# WizFi_Baseboard.net
KiCad netlist of a schematic drawn in EAGLE
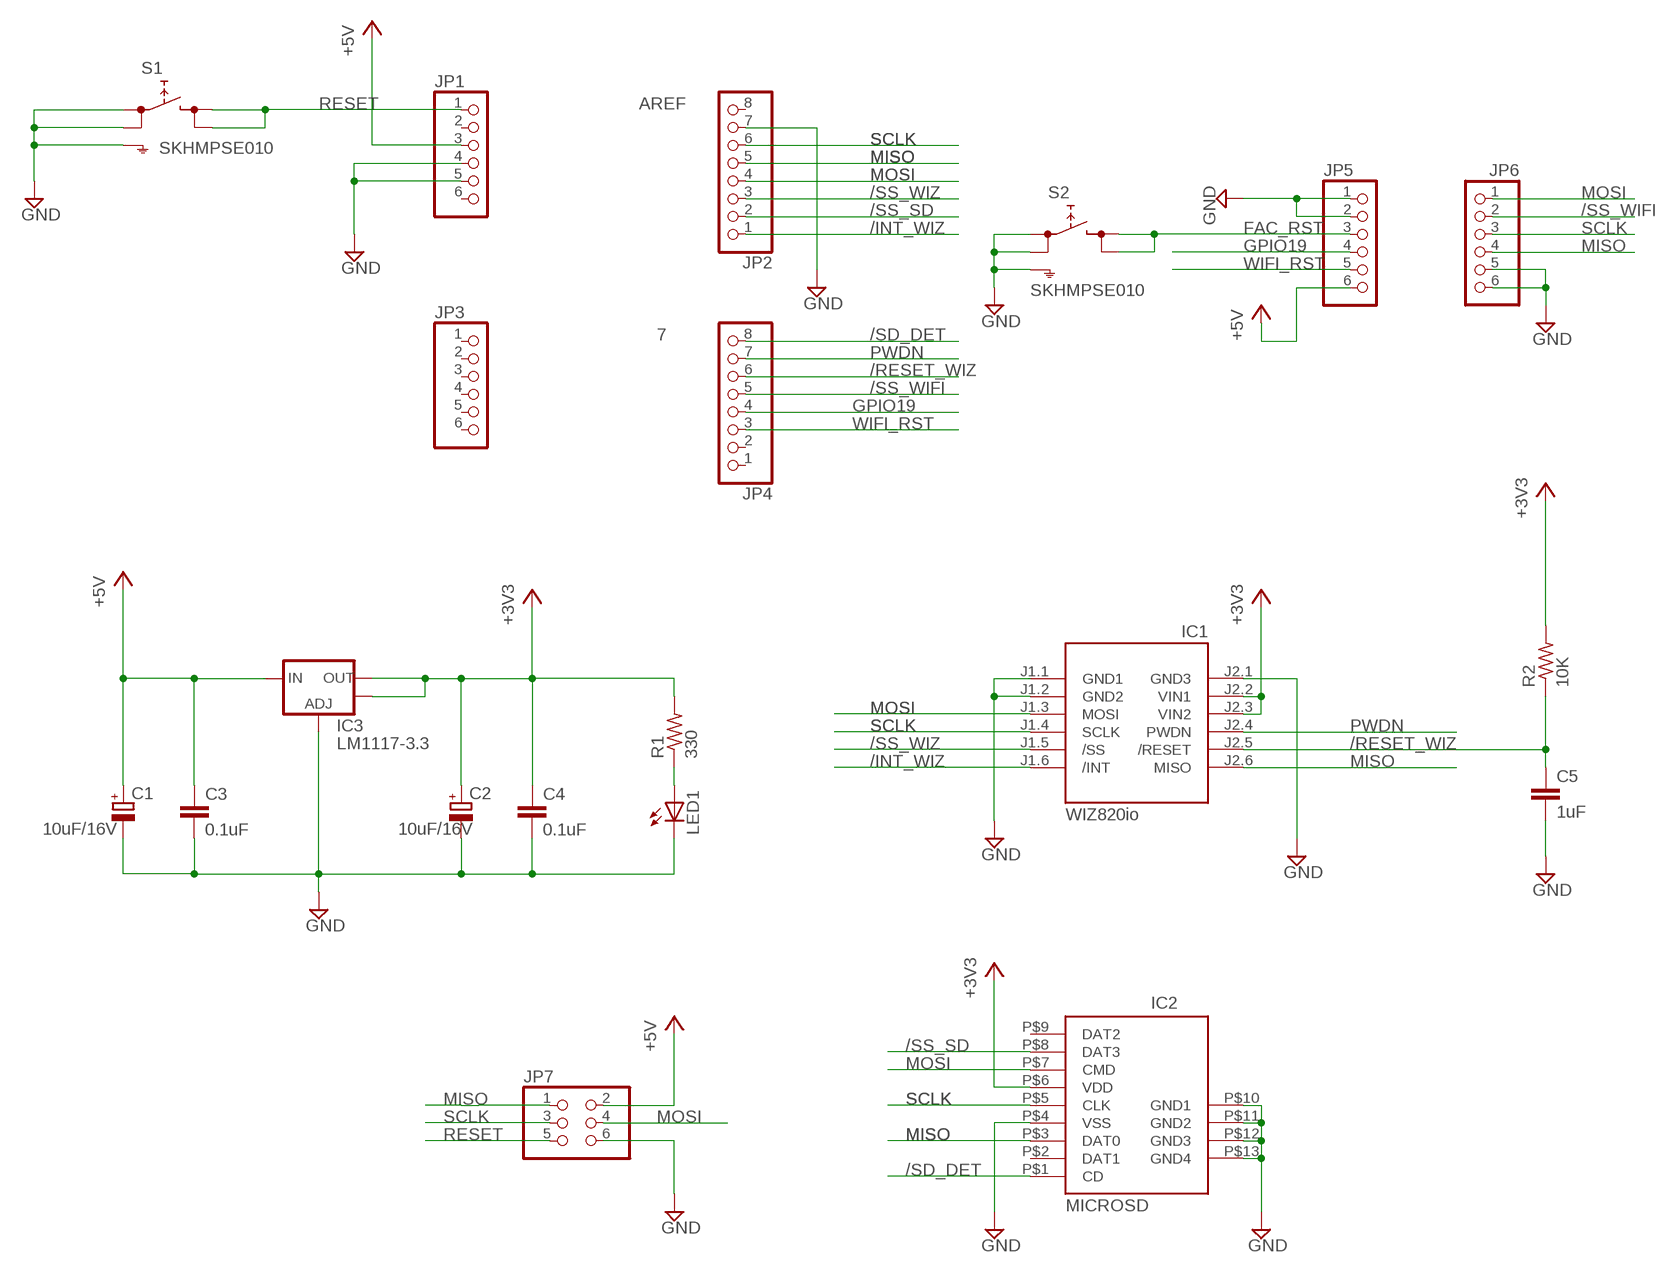
[diagram p0: schematic, sheet 1]

(export (version "E")
  (design (tool "Eeschema 10.0.6"))
  (components
    (comp (ref "C1")
      (value "10uF/16V")
      (footprint "eagle-import:CT3216")
      (libsource (lib "eagle-import") (part "CPOL-EUCT3216"))
    )
    (comp (ref "C2")
      (value "10uF/16V")
      (footprint "eagle-import:CT3216")
      (libsource (lib "eagle-import") (part "CPOL-EUCT3216"))
    )
    (comp (ref "C3")
      (value "0.1uF")
      (footprint "eagle-import:C0805")
      (libsource (lib "eagle-import") (part "C-EUC0805"))
    )
    (comp (ref "C4")
      (value "0.1uF")
      (footprint "eagle-import:C0805")
      (libsource (lib "eagle-import") (part "C-EUC0805"))
    )
    (comp (ref "C5")
      (value "1uF")
      (footprint "eagle-import:C0805")
      (libsource (lib "eagle-import") (part "C-EUC0805"))
    )
    (comp (ref "IC1")
      (value "WIZ820io")
      (footprint "eagle-import:WIZ820IO")
      (libsource (lib "eagle-import") (part "WIZ820IO_DEVICE'DUAL-IN-LINE-STAMP'"))
    )
    (comp (ref "IC2")
      (value "MICROSD")
      (footprint "eagle-import:MSDPAC")
      (libsource (lib "eagle-import") (part "MICROSD"))
    )
    (comp (ref "IC3")
      (value "LM1117-3.3")
      (footprint "eagle-import:SOT223")
      (libsource (lib "eagle-import") (part "V_REG_LM1117SOT223"))
    )
    (comp (ref "JP1")
      (value "PINHD-1X6")
      (footprint "eagle-import:1X06")
      (libsource (lib "eagle-import") (part "PINHD-1X6"))
    )
    (comp (ref "JP2")
      (value "PINHD-1X8")
      (footprint "eagle-import:1X08")
      (libsource (lib "eagle-import") (part "PINHD-1X8"))
    )
    (comp (ref "JP3")
      (value "PINHD-1X6")
      (footprint "eagle-import:1X06")
      (libsource (lib "eagle-import") (part "PINHD-1X6"))
    )
    (comp (ref "JP4")
      (value "PINHD-1X8")
      (footprint "eagle-import:1X08")
      (libsource (lib "eagle-import") (part "PINHD-1X8"))
    )
    (comp (ref "JP5")
      (value "PINHD-1X6")
      (footprint "eagle-import:1X06")
      (libsource (lib "eagle-import") (part "PINHD-1X6"))
    )
    (comp (ref "JP6")
      (value "PINHD-1X6")
      (footprint "eagle-import:1X06")
      (libsource (lib "eagle-import") (part "PINHD-1X6"))
    )
    (comp (ref "JP7")
      (value "PINHD-2X3")
      (footprint "eagle-import:2X03")
      (libsource (lib "eagle-import") (part "PINHD-2X3"))
    )
    (comp (ref "LED1")
      (value "LEDCHIP-LED0805")
      (footprint "eagle-import:CHIP-LED0805")
      (libsource (lib "eagle-import") (part "LEDCHIP-LED0805"))
    )
    (comp (ref "R1")
      (value "330")
      (footprint "eagle-import:R0805")
      (libsource (lib "eagle-import") (part "R-US_R0805"))
    )
    (comp (ref "R2")
      (value "10K")
      (footprint "eagle-import:R0805")
      (libsource (lib "eagle-import") (part "R-US_R0805"))
    )
    (comp (ref "S1")
      (value "SKHMPSE010")
      (footprint "eagle-import:SKHMPXE010")
      (libsource (lib "eagle-import") (part "SKHMPE010S"))
    )
    (comp (ref "S2")
      (value "SKHMPSE010")
      (footprint "eagle-import:SKHMPXE010")
      (libsource (lib "eagle-import") (part "SKHMPE010S"))
    )
  )
  (nets
    (net (code "1") (name "+3V3") (class "Default")
      (node (ref "C2") (pin "+") (pinfunction "+_+") (pintype "passive"))
      (node (ref "C4") (pin "1") (pinfunction "1_1") (pintype "passive"))
      (node (ref "IC1") (pin "J2.2") (pinfunction "VIN1_J2.2") (pintype "power_in"))
      (node (ref "IC1") (pin "J2.3") (pinfunction "VIN2_J2.3") (pintype "power_in"))
      (node (ref "IC2") (pin "P$6") (pinfunction "VDD_P$6") (pintype "power_in"))
      (node (ref "IC3") (pin "2") (pinfunction "OUT_2") (pintype "output"))
      (node (ref "IC3") (pin "4") (pinfunction "OUT_4") (pintype "output"))
      (node (ref "R1") (pin "2") (pinfunction "2_2") (pintype "passive"))
      (node (ref "R2") (pin "2") (pinfunction "2_2") (pintype "passive"))
    )
    (net (code "2") (name "+5V") (class "Default")
      (node (ref "C1") (pin "+") (pinfunction "+_+") (pintype "passive"))
      (node (ref "C3") (pin "1") (pinfunction "1_1") (pintype "passive"))
      (node (ref "IC3") (pin "3") (pinfunction "IN_3") (pintype "input"))
      (node (ref "JP1") (pin "3") (pinfunction "3_3") (pintype "passive"))
      (node (ref "JP5") (pin "6") (pinfunction "6_6") (pintype "passive"))
      (node (ref "JP7") (pin "2") (pinfunction "2_2") (pintype "passive"))
    )
    (net (code "3") (name "/FAC_RST") (class "Default")
      (node (ref "JP5") (pin "3") (pinfunction "3_3") (pintype "passive"))
      (node (ref "S2") (pin "3") (pinfunction "2.1_3") (pintype "passive"))
      (node (ref "S2") (pin "4") (pinfunction "2.2_4") (pintype "passive"))
    )
    (net (code "4") (name "/GPIO19") (class "Default")
      (node (ref "JP4") (pin "4") (pinfunction "4_4") (pintype "passive"))
      (node (ref "JP5") (pin "4") (pinfunction "4_4") (pintype "passive"))
    )
    (net (code "5") (name "/MISO") (class "Default")
      (node (ref "IC1") (pin "J2.6") (pinfunction "MISO_J2.6") (pintype "output"))
      (node (ref "IC2") (pin "P$3") (pinfunction "DAT0_P$3") (pintype "bidirectional"))
      (node (ref "JP2") (pin "5") (pinfunction "5_5") (pintype "passive"))
      (node (ref "JP6") (pin "4") (pinfunction "4_4") (pintype "passive"))
      (node (ref "JP7") (pin "1") (pinfunction "1_1") (pintype "passive"))
    )
    (net (code "6") (name "/MOSI") (class "Default")
      (node (ref "IC1") (pin "J1.3") (pinfunction "MOSI_J1.3") (pintype "input"))
      (node (ref "IC2") (pin "P$7") (pinfunction "CMD_P$7") (pintype "input"))
      (node (ref "JP2") (pin "4") (pinfunction "4_4") (pintype "passive"))
      (node (ref "JP6") (pin "1") (pinfunction "1_1") (pintype "passive"))
      (node (ref "JP7") (pin "4") (pinfunction "4_4") (pintype "passive"))
    )
    (net (code "7") (name "/PWDN") (class "Default")
      (node (ref "IC1") (pin "J2.4") (pinfunction "PWDN_J2.4") (pintype "input"))
      (node (ref "JP4") (pin "7") (pinfunction "7_7") (pintype "passive"))
    )
    (net (code "8") (name "/RESET") (class "Default")
      (node (ref "JP1") (pin "1") (pinfunction "1_1") (pintype "passive"))
      (node (ref "JP7") (pin "5") (pinfunction "5_5") (pintype "passive"))
      (node (ref "S1") (pin "3") (pinfunction "2.1_3") (pintype "passive"))
      (node (ref "S1") (pin "4") (pinfunction "2.2_4") (pintype "passive"))
    )
    (net (code "9") (name "/SCLK") (class "Default")
      (node (ref "IC1") (pin "J1.4") (pinfunction "SCLK_J1.4") (pintype "input"))
      (node (ref "IC2") (pin "P$5") (pinfunction "CLK_P$5") (pintype "input"))
      (node (ref "JP2") (pin "6") (pinfunction "6_6") (pintype "passive"))
      (node (ref "JP6") (pin "3") (pinfunction "3_3") (pintype "passive"))
      (node (ref "JP7") (pin "3") (pinfunction "3_3") (pintype "passive"))
    )
    (net (code "10") (name "/WIFI_RST") (class "Default")
      (node (ref "JP4") (pin "3") (pinfunction "3_3") (pintype "passive"))
      (node (ref "JP5") (pin "5") (pinfunction "5_5") (pintype "passive"))
    )
    (net (code "11") (name "/{slash}INT_WIZ") (class "Default")
      (node (ref "IC1") (pin "J1.6") (pinfunction "/INT_J1.6") (pintype "output"))
      (node (ref "JP2") (pin "1") (pinfunction "1_1") (pintype "passive"))
    )
    (net (code "12") (name "/{slash}RESET_WIZ") (class "Default")
      (node (ref "C5") (pin "1") (pinfunction "1_1") (pintype "passive"))
      (node (ref "IC1") (pin "J2.5") (pinfunction "/RESET_J2.5") (pintype "input"))
      (node (ref "JP4") (pin "6") (pinfunction "6_6") (pintype "passive"))
      (node (ref "R2") (pin "1") (pinfunction "1_1") (pintype "passive"))
    )
    (net (code "13") (name "/{slash}SD_DET") (class "Default")
      (node (ref "IC2") (pin "P$1") (pinfunction "CD_P$1") (pintype "bidirectional"))
      (node (ref "JP4") (pin "8") (pinfunction "8_8") (pintype "passive"))
    )
    (net (code "14") (name "/{slash}SS_SD") (class "Default")
      (node (ref "IC2") (pin "P$8") (pinfunction "DAT3_P$8") (pintype "bidirectional"))
      (node (ref "JP2") (pin "2") (pinfunction "2_2") (pintype "passive"))
    )
    (net (code "15") (name "/{slash}SS_WIFI") (class "Default")
      (node (ref "JP4") (pin "5") (pinfunction "5_5") (pintype "passive"))
      (node (ref "JP6") (pin "2") (pinfunction "2_2") (pintype "passive"))
    )
    (net (code "16") (name "/{slash}SS_WIZ") (class "Default")
      (node (ref "IC1") (pin "J1.5") (pinfunction "/SS_J1.5") (pintype "input"))
      (node (ref "JP2") (pin "3") (pinfunction "3_3") (pintype "passive"))
    )
    (net (code "17") (name "GND") (class "Default")
      (node (ref "C1") (pin "-") (pinfunction "-_-") (pintype "passive"))
      (node (ref "C2") (pin "-") (pinfunction "-_-") (pintype "passive"))
      (node (ref "C3") (pin "2") (pinfunction "2_2") (pintype "passive"))
      (node (ref "C4") (pin "2") (pinfunction "2_2") (pintype "passive"))
      (node (ref "C5") (pin "2") (pinfunction "2_2") (pintype "passive"))
      (node (ref "IC1") (pin "J1.1") (pinfunction "GND1_J1.1") (pintype "power_in"))
      (node (ref "IC1") (pin "J1.2") (pinfunction "GND2_J1.2") (pintype "power_in"))
      (node (ref "IC1") (pin "J2.1") (pinfunction "GND3_J2.1") (pintype "power_in"))
      (node (ref "IC2") (pin "P$10") (pinfunction "GND1_P$10") (pintype "power_in"))
      (node (ref "IC2") (pin "P$11") (pinfunction "GND2_P$11") (pintype "power_in"))
      (node (ref "IC2") (pin "P$12") (pinfunction "GND3_P$12") (pintype "power_in"))
      (node (ref "IC2") (pin "P$13") (pinfunction "GND4_P$13") (pintype "power_in"))
      (node (ref "IC2") (pin "P$4") (pinfunction "VSS_P$4") (pintype "power_in"))
      (node (ref "IC3") (pin "1") (pinfunction "ADJ_1") (pintype "input"))
      (node (ref "JP1") (pin "4") (pinfunction "4_4") (pintype "passive"))
      (node (ref "JP1") (pin "5") (pinfunction "5_5") (pintype "passive"))
      (node (ref "JP2") (pin "7") (pinfunction "7_7") (pintype "passive"))
      (node (ref "JP5") (pin "1") (pinfunction "1_1") (pintype "passive"))
      (node (ref "JP5") (pin "2") (pinfunction "2_2") (pintype "passive"))
      (node (ref "JP6") (pin "5") (pinfunction "5_5") (pintype "passive"))
      (node (ref "JP6") (pin "6") (pinfunction "6_6") (pintype "passive"))
      (node (ref "JP7") (pin "6") (pinfunction "6_6") (pintype "passive"))
      (node (ref "LED1") (pin "C") (pinfunction "C_C") (pintype "passive"))
      (node (ref "S1") (pin "1") (pinfunction "1.1_1") (pintype "passive"))
      (node (ref "S1") (pin "2") (pinfunction "1.2_2") (pintype "passive"))
      (node (ref "S1") (pin "5") (pinfunction "SH_5") (pintype "passive"))
      (node (ref "S2") (pin "1") (pinfunction "1.1_1") (pintype "passive"))
      (node (ref "S2") (pin "2") (pinfunction "1.2_2") (pintype "passive"))
      (node (ref "S2") (pin "5") (pinfunction "SH_5") (pintype "passive"))
    )
    (net (code "18") (name "Net-(LED1-PadA)") (class "Default")
      (node (ref "LED1") (pin "A") (pinfunction "A_A") (pintype "passive"))
      (node (ref "R1") (pin "1") (pinfunction "1_1") (pintype "passive"))
    )
    (net (code "19") (name "unconnected-(IC2-DAT1-PadP$2)") (class "Default")
      (node (ref "IC2") (pin "P$2") (pinfunction "DAT1_P$2") (pintype "bidirectional"))
    )
    (net (code "20") (name "unconnected-(IC2-DAT2-PadP$9)") (class "Default")
      (node (ref "IC2") (pin "P$9") (pinfunction "DAT2_P$9") (pintype "bidirectional"))
    )
    (net (code "21") (name "unconnected-(JP1-Pad2)") (class "Default")
      (node (ref "JP1") (pin "2") (pinfunction "2_2") (pintype "passive"))
    )
    (net (code "22") (name "unconnected-(JP1-Pad6)") (class "Default")
      (node (ref "JP1") (pin "6") (pinfunction "6_6") (pintype "passive"))
    )
    (net (code "23") (name "unconnected-(JP2-Pad8)") (class "Default")
      (node (ref "JP2") (pin "8") (pinfunction "8_8") (pintype "passive"))
    )
    (net (code "24") (name "unconnected-(JP3-Pad1)") (class "Default")
      (node (ref "JP3") (pin "1") (pinfunction "1_1") (pintype "passive"))
    )
    (net (code "25") (name "unconnected-(JP3-Pad2)") (class "Default")
      (node (ref "JP3") (pin "2") (pinfunction "2_2") (pintype "passive"))
    )
    (net (code "26") (name "unconnected-(JP3-Pad3)") (class "Default")
      (node (ref "JP3") (pin "3") (pinfunction "3_3") (pintype "passive"))
    )
    (net (code "27") (name "unconnected-(JP3-Pad4)") (class "Default")
      (node (ref "JP3") (pin "4") (pinfunction "4_4") (pintype "passive"))
    )
    (net (code "28") (name "unconnected-(JP3-Pad5)") (class "Default")
      (node (ref "JP3") (pin "5") (pinfunction "5_5") (pintype "passive"))
    )
    (net (code "29") (name "unconnected-(JP3-Pad6)") (class "Default")
      (node (ref "JP3") (pin "6") (pinfunction "6_6") (pintype "passive"))
    )
    (net (code "30") (name "unconnected-(JP4-Pad1)") (class "Default")
      (node (ref "JP4") (pin "1") (pinfunction "1_1") (pintype "passive"))
    )
    (net (code "31") (name "unconnected-(JP4-Pad2)") (class "Default")
      (node (ref "JP4") (pin "2") (pinfunction "2_2") (pintype "passive"))
    )
  )
)
